# mic-amplifier.net
KiCad netlist of a schematic drawn in EAGLE
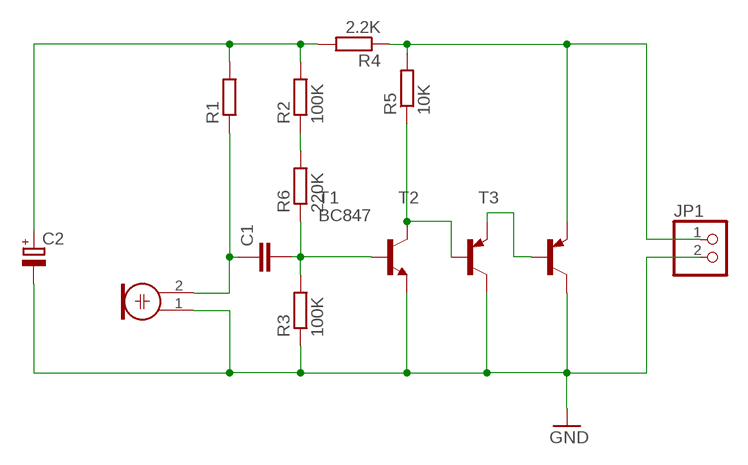
[diagram p0: schematic, sheet 1]

(export (version "E")
  (design (tool "Eeschema 10.0.6"))
  (components
    (comp (ref "C1")
      (value "C-EUC1206")
      (footprint "eagle-import:C1206")
      (libsource (lib "eagle-import") (part "C-EUC1206"))
    )
    (comp (ref "C2")
      (value "CPOL-EUE2,5-6E")
      (footprint "eagle-import:E2,5-6E")
      (libsource (lib "eagle-import") (part "CPOL-EUE2,5-6E"))
    )
    (comp (ref "JP1")
      (value "PINHD-1X2")
      (footprint "eagle-import:1X02")
      (libsource (lib "eagle-import") (part "PINHD-1X2"))
    )
    (comp (ref "M1")
      (value "ELECTRET_MICROPHON-WM-61B")
      (footprint "eagle-import:WM-61B")
      (libsource (lib "eagle-import") (part "ELECTRET_MICROPHON-WM-61B"))
    )
    (comp (ref "R1")
      (value "R-EU_R0805")
      (footprint "eagle-import:R0805")
      (libsource (lib "eagle-import") (part "R-EU_R0805"))
    )
    (comp (ref "R2")
      (value "100K")
      (footprint "eagle-import:R0805")
      (libsource (lib "eagle-import") (part "R-EU_R0805"))
    )
    (comp (ref "R3")
      (value "100K")
      (footprint "eagle-import:R0805")
      (libsource (lib "eagle-import") (part "R-EU_R0805"))
    )
    (comp (ref "R4")
      (value "2.2K")
      (footprint "eagle-import:R1206")
      (libsource (lib "eagle-import") (part "R-EU_R1206"))
    )
    (comp (ref "R5")
      (value "10K")
      (footprint "eagle-import:R1206")
      (libsource (lib "eagle-import") (part "R-EU_R1206"))
    )
    (comp (ref "R6")
      (value "220K")
      (footprint "eagle-import:R1206")
      (libsource (lib "eagle-import") (part "R-EU_R1206"))
    )
    (comp (ref "T1")
      (value "BC847")
      (footprint "eagle-import:SOT23")
      (libsource (lib "eagle-import") (part "BC847"))
    )
    (comp (ref "T2")
      (value "BC857B-PNP-SOT23-BEC")
      (footprint "eagle-import:SOT23-BEC")
      (libsource (lib "eagle-import") (part "-PNP-SOT23-BECBC857B"))
    )
    (comp (ref "T3")
      (value "BC857B-PNP-SOT23-BEC")
      (footprint "eagle-import:SOT23-BEC")
      (libsource (lib "eagle-import") (part "-PNP-SOT23-BECBC857B"))
    )
  )
  (nets
    (net (code "1") (name "GND") (class "Default")
      (node (ref "C2") (pin "-") (pinfunction "-_-") (pintype "passive"))
      (node (ref "JP1") (pin "2") (pinfunction "2_2") (pintype "passive"))
      (node (ref "M1") (pin "1") (pinfunction "1_1") (pintype "passive"))
      (node (ref "R3") (pin "1") (pinfunction "1_1") (pintype "passive"))
      (node (ref "T1") (pin "2") (pinfunction "E_2") (pintype "passive"))
      (node (ref "T2") (pin "C") (pinfunction "C_C") (pintype "passive"))
      (node (ref "T3") (pin "C") (pinfunction "C_C") (pintype "passive"))
    )
    (net (code "2") (name "Net-(C1-Pad1)") (class "Default")
      (node (ref "C1") (pin "1") (pinfunction "1_1") (pintype "passive"))
      (node (ref "M1") (pin "2") (pinfunction "2_2") (pintype "passive"))
      (node (ref "R1") (pin "1") (pinfunction "1_1") (pintype "passive"))
    )
    (net (code "3") (name "Net-(C2-Pad+)") (class "Default")
      (node (ref "C2") (pin "+") (pinfunction "+_+") (pintype "passive"))
      (node (ref "R1") (pin "2") (pinfunction "2_2") (pintype "passive"))
      (node (ref "R2") (pin "2") (pinfunction "2_2") (pintype "passive"))
      (node (ref "R4") (pin "2") (pinfunction "2_2") (pintype "passive"))
    )
    (net (code "4") (name "Net-(JP1-Pad1)") (class "Default")
      (node (ref "JP1") (pin "1") (pinfunction "1_1") (pintype "passive"))
      (node (ref "R4") (pin "1") (pinfunction "1_1") (pintype "passive"))
      (node (ref "R5") (pin "2") (pinfunction "2_2") (pintype "passive"))
      (node (ref "T3") (pin "E") (pinfunction "E_E") (pintype "passive"))
    )
    (net (code "5") (name "Net-(R2-Pad1)") (class "Default")
      (node (ref "R2") (pin "1") (pinfunction "1_1") (pintype "passive"))
      (node (ref "R6") (pin "2") (pinfunction "2_2") (pintype "passive"))
    )
    (net (code "6") (name "Net-(T1-B)") (class "Default")
      (node (ref "C1") (pin "2") (pinfunction "2_2") (pintype "passive"))
      (node (ref "R3") (pin "2") (pinfunction "2_2") (pintype "passive"))
      (node (ref "R6") (pin "1") (pinfunction "1_1") (pintype "passive"))
      (node (ref "T1") (pin "1") (pinfunction "B_1") (pintype "passive"))
    )
    (net (code "7") (name "Net-(T1-C)") (class "Default")
      (node (ref "R5") (pin "1") (pinfunction "1_1") (pintype "passive"))
      (node (ref "T1") (pin "3") (pinfunction "C_3") (pintype "passive"))
      (node (ref "T2") (pin "B") (pinfunction "B_B") (pintype "passive"))
    )
    (net (code "8") (name "Net-(T2-PadE)") (class "Default")
      (node (ref "T2") (pin "E") (pinfunction "E_E") (pintype "passive"))
      (node (ref "T3") (pin "B") (pinfunction "B_B") (pintype "passive"))
    )
  )
)
